# Outputs.net
KiCad netlist of a schematic drawn in Altium Designer
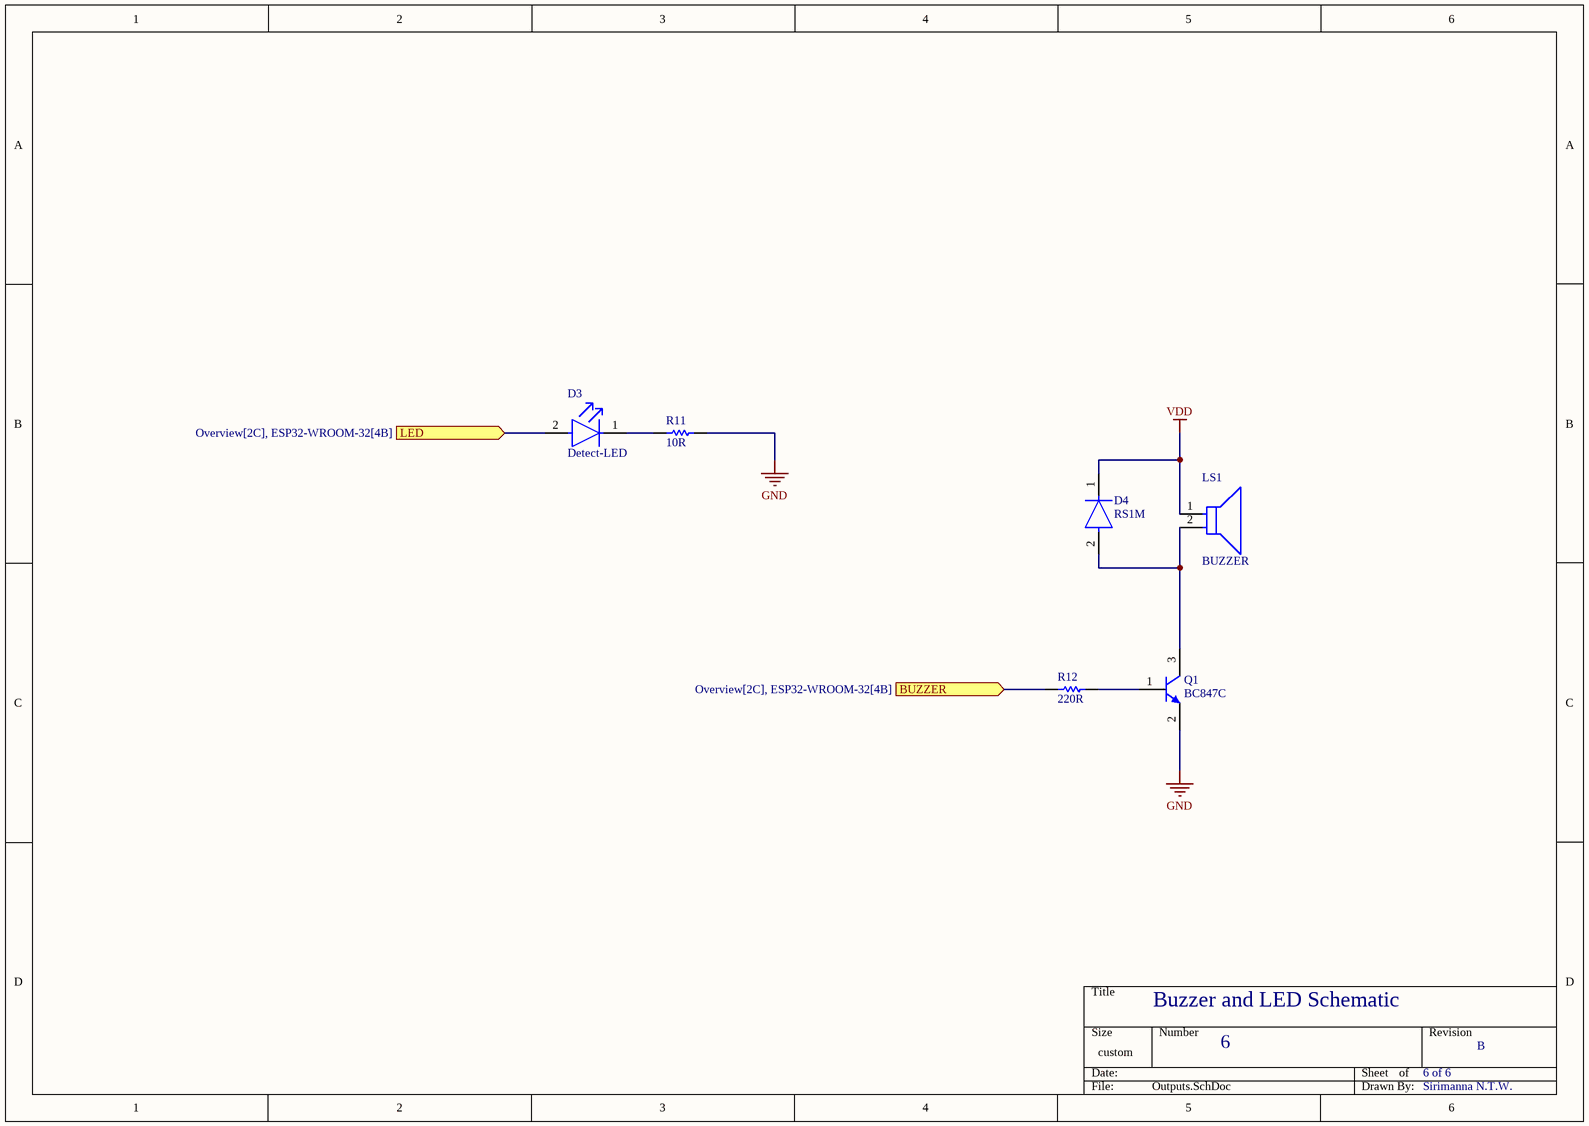
[diagram p0: Outputs.SchDoc]

(export (version "E")
  (design (tool "Eeschema 10.0.6"))
  (components
    (comp (ref "D3")
      (value "Detect-LED")
      (footprint "FP-6_544-5255_01-4-MFG")
      (description "TLLG4400 Led, Pcb, Green, 0.63MCD, 3MM, T-1, 7MA, 1.9V, 565NM, 25DEG, 20V, 20MW, -40")
      (libsource (lib "Altium Content Vault") (part "8706943c75ba83719d021d2fdc84c58"))
    )
    (comp (ref "D4")
      (value "RS1M")
      (footprint "FP-403AE-MFG")
      (description "DIODE GEN PURP 1KV 1A SMA")
      (fields
        (field (name "OCTOPART") "https://octopart.com/rs1m-on+semiconductor-84331238")
        (field (name "MANUFACTURER") "ON Semiconductor")
      )
      (libsource (lib "Altium Content Vault") (part "d7152d700b627762746794eb795d46e"))
    )
    (comp (ref "LS1")
      (value "BUZZER")
      (footprint "FP-PS1440P02BT-MFG")
      (description "AUDIO PIEZO TRANSDUCER 30V TH")
      (libsource (lib "Altium Content Vault") (part "5f581d31613f872430949aa526fd155"))
    )
    (comp (ref "Q1")
      (value "BC847C")
      (footprint "INF-SOT23_M")
      (description "NPN Silicon AF Transistor, 45 V VCEO, 100 mA IC, SOT23, Reel, Green")
      (fields (field (name "MANUFACTURER") "Infineon") (field (name "PARTNUMBER") "BC847B"))
      (libsource (lib "Altium Content Vault") (part "INF-BJTNPN-BEC-3"))
    )
    (comp (ref "R11")
      (value "10R")
      (footprint "RESC2013X60X35ML10T20")
      (description "Chip Resistor, 10 Ohm, +/- 1%, 0.125 W, -55 to 155 degC, 0805 (2012 Metric), RoHS, Tape and Reel")
      (fields (field (name "MANUFACTURER") "Yageo") (field (name "TOLERANCE") "1%"))
      (libsource (lib "Altium Content Vault") (part "RES-2"))
    )
    (comp (ref "R12")
      (value "220R")
      (footprint "RESC2013X70X40LL20T20")
      (fields (field (name "PART NUMBER") "ERJ6ENF2200V") (field (name "MANUFACTURER") "Panasonic"))
      (libsource (lib "Altium Content Vault") (part "RES"))
    )
  )
  (nets
    (net (code "1") (name "/BUZZER") (class "Default")
      (node (ref "R12") (pin "1") (pinfunction "1_1") (pintype "passive"))
    )
    (net (code "2") (name "/LED") (class "Default")
      (node (ref "D3") (pin "2") (pinfunction "A_2") (pintype "passive"))
    )
    (net (code "3") (name "GND") (class "Default")
      (node (ref "Q1") (pin "2") (pinfunction "E_2") (pintype "passive"))
      (node (ref "R11") (pin "2") (pinfunction "2_2") (pintype "passive"))
    )
    (net (code "4") (name "Net-(D3-C)") (class "Default")
      (node (ref "D3") (pin "1") (pinfunction "C_1") (pintype "passive"))
      (node (ref "R11") (pin "1") (pinfunction "1_1") (pintype "passive"))
    )
    (net (code "5") (name "Net-(D4-A)") (class "Default")
      (node (ref "D4") (pin "2") (pinfunction "A_2") (pintype "passive"))
      (node (ref "LS1") (pin "2") (pinfunction "2_2") (pintype "passive"))
      (node (ref "Q1") (pin "3") (pinfunction "C_3") (pintype "passive"))
    )
    (net (code "6") (name "Net-(Q1-B)") (class "Default")
      (node (ref "Q1") (pin "1") (pinfunction "B_1") (pintype "passive"))
      (node (ref "R12") (pin "2") (pinfunction "2_2") (pintype "passive"))
    )
    (net (code "7") (name "VDD") (class "Default")
      (node (ref "D4") (pin "1") (pinfunction "C_1") (pintype "passive"))
      (node (ref "LS1") (pin "1") (pinfunction "1_1") (pintype "passive"))
    )
  )
)
